# Blumen_Frente.net
KiCad netlist of a schematic drawn in EAGLE
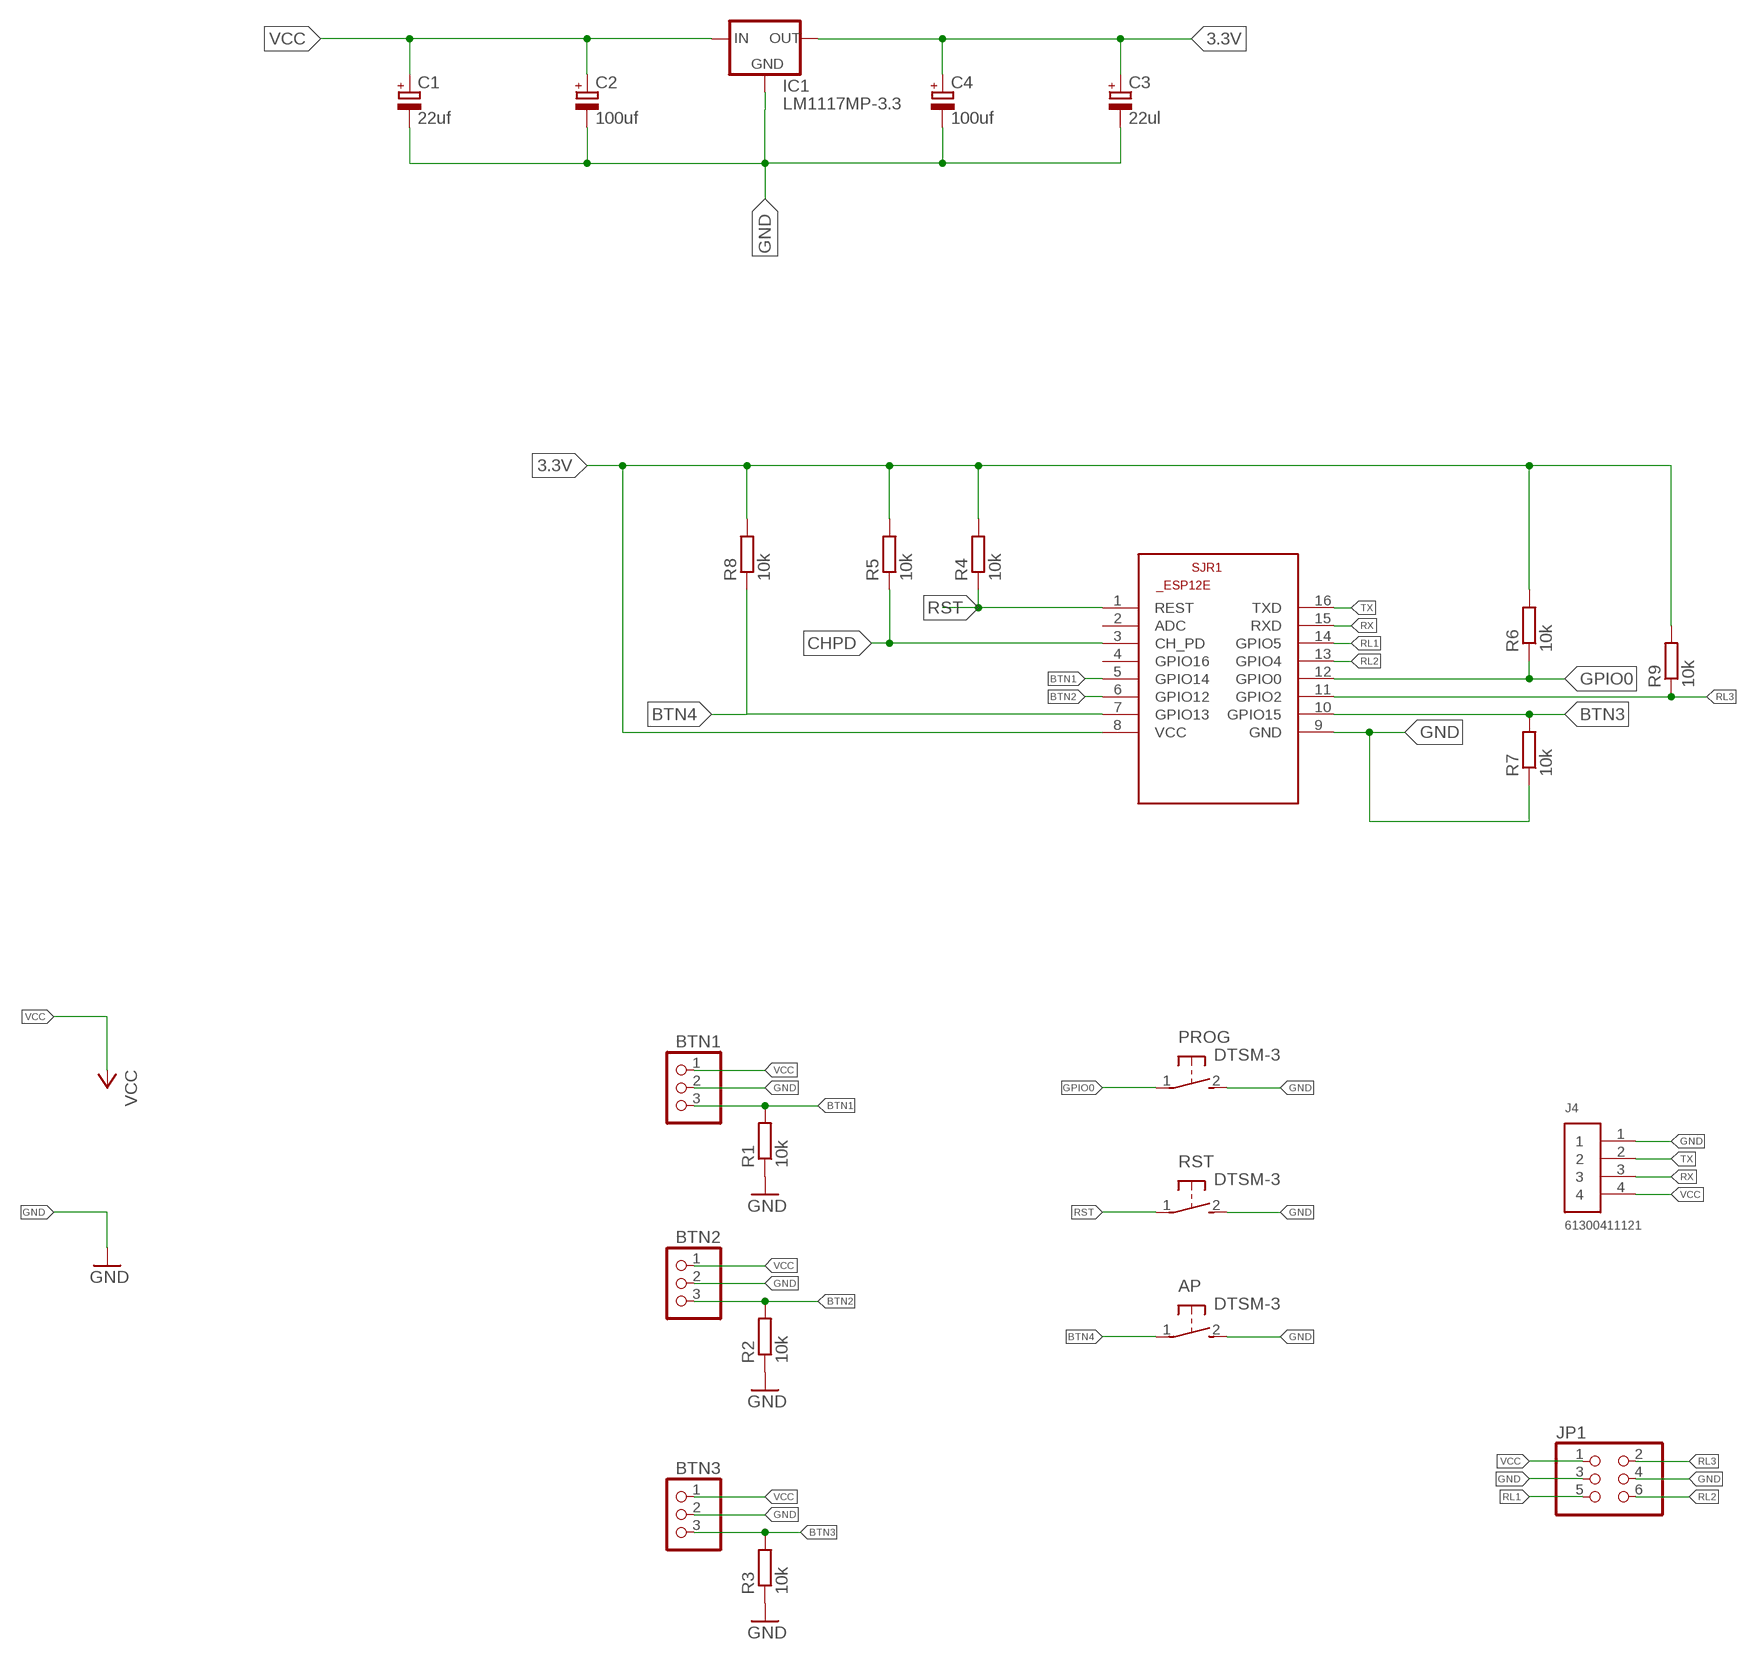
[diagram p0: schematic, sheet 1]

(export (version "E")
  (design (tool "Eeschema 10.0.6"))
  (components
    (comp (ref "AP")
      (value "DTSM-3")
      (footprint "eagle-import:DTSM-3")
      (libsource (lib "eagle-import") (part "DTSM-3"))
    )
    (comp (ref "BTN1")
      (value "PINHD-1X3")
      (footprint "eagle-import:1X03")
      (libsource (lib "eagle-import") (part "PINHD-1X3"))
    )
    (comp (ref "BTN2")
      (value "PINHD-1X3")
      (footprint "eagle-import:1X03")
      (libsource (lib "eagle-import") (part "PINHD-1X3"))
    )
    (comp (ref "BTN3")
      (value "PINHD-1X3")
      (footprint "eagle-import:1X03")
      (libsource (lib "eagle-import") (part "PINHD-1X3"))
    )
    (comp (ref "C1")
      (value "22uf")
      (footprint "eagle-import:153CLV-0505")
      (libsource (lib "eagle-import") (part "CPOL-EU153CLV-0505"))
    )
    (comp (ref "C2")
      (value "100uf")
      (footprint "eagle-import:153CLV-0605")
      (libsource (lib "eagle-import") (part "CPOL-EU153CLV-0605"))
    )
    (comp (ref "C3")
      (value "22ul")
      (footprint "eagle-import:153CLV-0505")
      (libsource (lib "eagle-import") (part "CPOL-EU153CLV-0505"))
    )
    (comp (ref "C4")
      (value "100uf")
      (footprint "eagle-import:153CLV-0605")
      (libsource (lib "eagle-import") (part "CPOL-EU153CLV-0605"))
    )
    (comp (ref "IC1")
      (value "LM1117MP-3.3")
      (footprint "eagle-import:SOT223")
      (fields (field (name "MF") "Texas Instruments"))
      (libsource (lib "eagle-import") (part "LM1117?-MP3.3"))
    )
    (comp (ref "J4")
      (value "61300411121")
      (footprint "eagle-import:61300411121")
      (fields
        (field (name "DIGI_KEY_PART_NUMBER") "732-5317-ND")
        (field (name "MANUFACTURER") "Wurth Electronics Inc.")
        (field (name "CREATED_BY") "PCBLayout.com")
      )
      (libsource (lib "eagle-import") (part "61300411121"))
    )
    (comp (ref "JP1")
      (value "PINHD-2X3")
      (footprint "eagle-import:2X03")
      (libsource (lib "eagle-import") (part "PINHD-2X3"))
    )
    (comp (ref "PROG")
      (value "DTSM-3")
      (footprint "eagle-import:DTSM-3")
      (libsource (lib "eagle-import") (part "DTSM-3"))
    )
    (comp (ref "R1")
      (value "10k")
      (footprint "eagle-import:R0805")
      (libsource (lib "eagle-import") (part "R-EU_R0805"))
    )
    (comp (ref "R2")
      (value "10k")
      (footprint "eagle-import:R0805")
      (libsource (lib "eagle-import") (part "R-EU_R0805"))
    )
    (comp (ref "R3")
      (value "10k")
      (footprint "eagle-import:R0805")
      (libsource (lib "eagle-import") (part "R-EU_R0805"))
    )
    (comp (ref "R4")
      (value "10k")
      (footprint "eagle-import:R0805")
      (libsource (lib "eagle-import") (part "R-EU_R0805"))
    )
    (comp (ref "R5")
      (value "10k")
      (footprint "eagle-import:R0805")
      (libsource (lib "eagle-import") (part "R-EU_R0805"))
    )
    (comp (ref "R6")
      (value "10k")
      (footprint "eagle-import:R0805")
      (libsource (lib "eagle-import") (part "R-EU_R0805"))
    )
    (comp (ref "R7")
      (value "10k")
      (footprint "eagle-import:R0805")
      (libsource (lib "eagle-import") (part "R-EU_R0805"))
    )
    (comp (ref "R8")
      (value "10k")
      (footprint "eagle-import:R0805")
      (libsource (lib "eagle-import") (part "R-EU_R0805"))
    )
    (comp (ref "R9")
      (value "10k")
      (footprint "eagle-import:R0805")
      (libsource (lib "eagle-import") (part "R-EU_R0805"))
    )
    (comp (ref "RST")
      (value "DTSM-3")
      (footprint "eagle-import:DTSM-3")
      (libsource (lib "eagle-import") (part "DTSM-3"))
    )
    (comp (ref "SJR1")
      (value "ESP8266-12EESP12E")
      (footprint "eagle-import:ESP8266-ESP12E")
      (libsource (lib "eagle-import") (part "ESP8266-12EESP12E"))
    )
  )
  (nets
    (net (code "1") (name "3.3V") (class "Default")
      (node (ref "C3") (pin "+") (pinfunction "+_+") (pintype "passive"))
      (node (ref "C4") (pin "+") (pinfunction "+_+") (pintype "passive"))
      (node (ref "IC1") (pin "2") (pinfunction "OUT_2") (pintype "passive"))
      (node (ref "IC1") (pin "4") (pinfunction "OUT_4") (pintype "passive"))
      (node (ref "R4") (pin "2") (pinfunction "2_2") (pintype "passive"))
      (node (ref "R5") (pin "2") (pinfunction "2_2") (pintype "passive"))
      (node (ref "R6") (pin "2") (pinfunction "2_2") (pintype "passive"))
      (node (ref "R8") (pin "2") (pinfunction "2_2") (pintype "passive"))
      (node (ref "R9") (pin "2") (pinfunction "2_2") (pintype "passive"))
      (node (ref "SJR1") (pin "8") (pinfunction "VCC_8") (pintype "bidirectional"))
    )
    (net (code "2") (name "BTN1") (class "Default")
      (node (ref "BTN1") (pin "3") (pinfunction "3_3") (pintype "passive"))
      (node (ref "R1") (pin "2") (pinfunction "2_2") (pintype "passive"))
      (node (ref "SJR1") (pin "5") (pinfunction "GPIO14_5") (pintype "bidirectional"))
    )
    (net (code "3") (name "BTN2") (class "Default")
      (node (ref "BTN2") (pin "3") (pinfunction "3_3") (pintype "passive"))
      (node (ref "R2") (pin "2") (pinfunction "2_2") (pintype "passive"))
      (node (ref "SJR1") (pin "6") (pinfunction "GPIO12_6") (pintype "bidirectional"))
    )
    (net (code "4") (name "BTN3") (class "Default")
      (node (ref "BTN3") (pin "3") (pinfunction "3_3") (pintype "passive"))
      (node (ref "R3") (pin "2") (pinfunction "2_2") (pintype "passive"))
      (node (ref "R7") (pin "2") (pinfunction "2_2") (pintype "passive"))
      (node (ref "SJR1") (pin "10") (pinfunction "GPIO15_10") (pintype "bidirectional"))
    )
    (net (code "5") (name "BTN4") (class "Default")
      (node (ref "AP") (pin "1") (pinfunction "1_1") (pintype "passive"))
      (node (ref "R8") (pin "1") (pinfunction "1_1") (pintype "passive"))
      (node (ref "SJR1") (pin "7") (pinfunction "GPIO13_7") (pintype "bidirectional"))
    )
    (net (code "6") (name "CHPD") (class "Default")
      (node (ref "R5") (pin "1") (pinfunction "1_1") (pintype "passive"))
      (node (ref "SJR1") (pin "3") (pinfunction "CH_PD_3") (pintype "bidirectional"))
    )
    (net (code "7") (name "GND") (class "Default")
      (node (ref "AP") (pin "2") (pinfunction "2_2") (pintype "passive"))
      (node (ref "BTN1") (pin "2") (pinfunction "2_2") (pintype "passive"))
      (node (ref "BTN2") (pin "2") (pinfunction "2_2") (pintype "passive"))
      (node (ref "BTN3") (pin "2") (pinfunction "2_2") (pintype "passive"))
      (node (ref "C1") (pin "-") (pinfunction "-_-") (pintype "passive"))
      (node (ref "C2") (pin "-") (pinfunction "-_-") (pintype "passive"))
      (node (ref "C3") (pin "-") (pinfunction "-_-") (pintype "passive"))
      (node (ref "C4") (pin "-") (pinfunction "-_-") (pintype "passive"))
      (node (ref "IC1") (pin "1") (pinfunction "GND_1") (pintype "input"))
      (node (ref "J4") (pin "1") (pinfunction "1_1") (pintype "passive"))
      (node (ref "JP1") (pin "3") (pinfunction "3_3") (pintype "passive"))
      (node (ref "JP1") (pin "4") (pinfunction "4_4") (pintype "passive"))
      (node (ref "PROG") (pin "2") (pinfunction "2_2") (pintype "passive"))
      (node (ref "R1") (pin "1") (pinfunction "1_1") (pintype "passive"))
      (node (ref "R2") (pin "1") (pinfunction "1_1") (pintype "passive"))
      (node (ref "R3") (pin "1") (pinfunction "1_1") (pintype "passive"))
      (node (ref "R7") (pin "1") (pinfunction "1_1") (pintype "passive"))
      (node (ref "RST") (pin "2") (pinfunction "2_2") (pintype "passive"))
      (node (ref "SJR1") (pin "9") (pinfunction "GND_9") (pintype "bidirectional"))
    )
    (net (code "8") (name "GPIO0") (class "Default")
      (node (ref "PROG") (pin "1") (pinfunction "1_1") (pintype "passive"))
      (node (ref "R6") (pin "1") (pinfunction "1_1") (pintype "passive"))
      (node (ref "SJR1") (pin "12") (pinfunction "GPIO0_12") (pintype "bidirectional"))
    )
    (net (code "9") (name "RL1") (class "Default")
      (node (ref "JP1") (pin "5") (pinfunction "5_5") (pintype "passive"))
      (node (ref "SJR1") (pin "14") (pinfunction "GPIO5_14") (pintype "bidirectional"))
    )
    (net (code "10") (name "RL2") (class "Default")
      (node (ref "JP1") (pin "6") (pinfunction "6_6") (pintype "passive"))
      (node (ref "SJR1") (pin "13") (pinfunction "GPIO4_13") (pintype "bidirectional"))
    )
    (net (code "11") (name "RL3") (class "Default")
      (node (ref "JP1") (pin "2") (pinfunction "2_2") (pintype "passive"))
      (node (ref "R9") (pin "1") (pinfunction "1_1") (pintype "passive"))
      (node (ref "SJR1") (pin "11") (pinfunction "GPIO2_11") (pintype "bidirectional"))
    )
    (net (code "12") (name "RST") (class "Default")
      (node (ref "R4") (pin "1") (pinfunction "1_1") (pintype "passive"))
      (node (ref "RST") (pin "1") (pinfunction "1_1") (pintype "passive"))
      (node (ref "SJR1") (pin "1") (pinfunction "REST_1") (pintype "bidirectional"))
    )
    (net (code "13") (name "RX") (class "Default")
      (node (ref "J4") (pin "3") (pinfunction "3_3") (pintype "passive"))
      (node (ref "SJR1") (pin "15") (pinfunction "RXD_15") (pintype "bidirectional"))
    )
    (net (code "14") (name "TX") (class "Default")
      (node (ref "J4") (pin "2") (pinfunction "2_2") (pintype "passive"))
      (node (ref "SJR1") (pin "16") (pinfunction "TXD_16") (pintype "bidirectional"))
    )
    (net (code "15") (name "VCC") (class "Default")
      (node (ref "BTN1") (pin "1") (pinfunction "1_1") (pintype "passive"))
      (node (ref "BTN2") (pin "1") (pinfunction "1_1") (pintype "passive"))
      (node (ref "BTN3") (pin "1") (pinfunction "1_1") (pintype "passive"))
      (node (ref "C1") (pin "+") (pinfunction "+_+") (pintype "passive"))
      (node (ref "C2") (pin "+") (pinfunction "+_+") (pintype "passive"))
      (node (ref "IC1") (pin "3") (pinfunction "IN_3") (pintype "input"))
      (node (ref "J4") (pin "4") (pinfunction "4_4") (pintype "passive"))
      (node (ref "JP1") (pin "1") (pinfunction "1_1") (pintype "passive"))
    )
    (net (code "16") (name "unconnected-(SJR1-ADC-Pad2)") (class "Default")
      (node (ref "SJR1") (pin "2") (pinfunction "ADC_2") (pintype "bidirectional"))
    )
    (net (code "17") (name "unconnected-(SJR1-GPIO16-Pad4)") (class "Default")
      (node (ref "SJR1") (pin "4") (pinfunction "GPIO16_4") (pintype "bidirectional"))
    )
  )
)
